# 03_ICs.net
KiCad netlist of a schematic drawn in Altium Designer
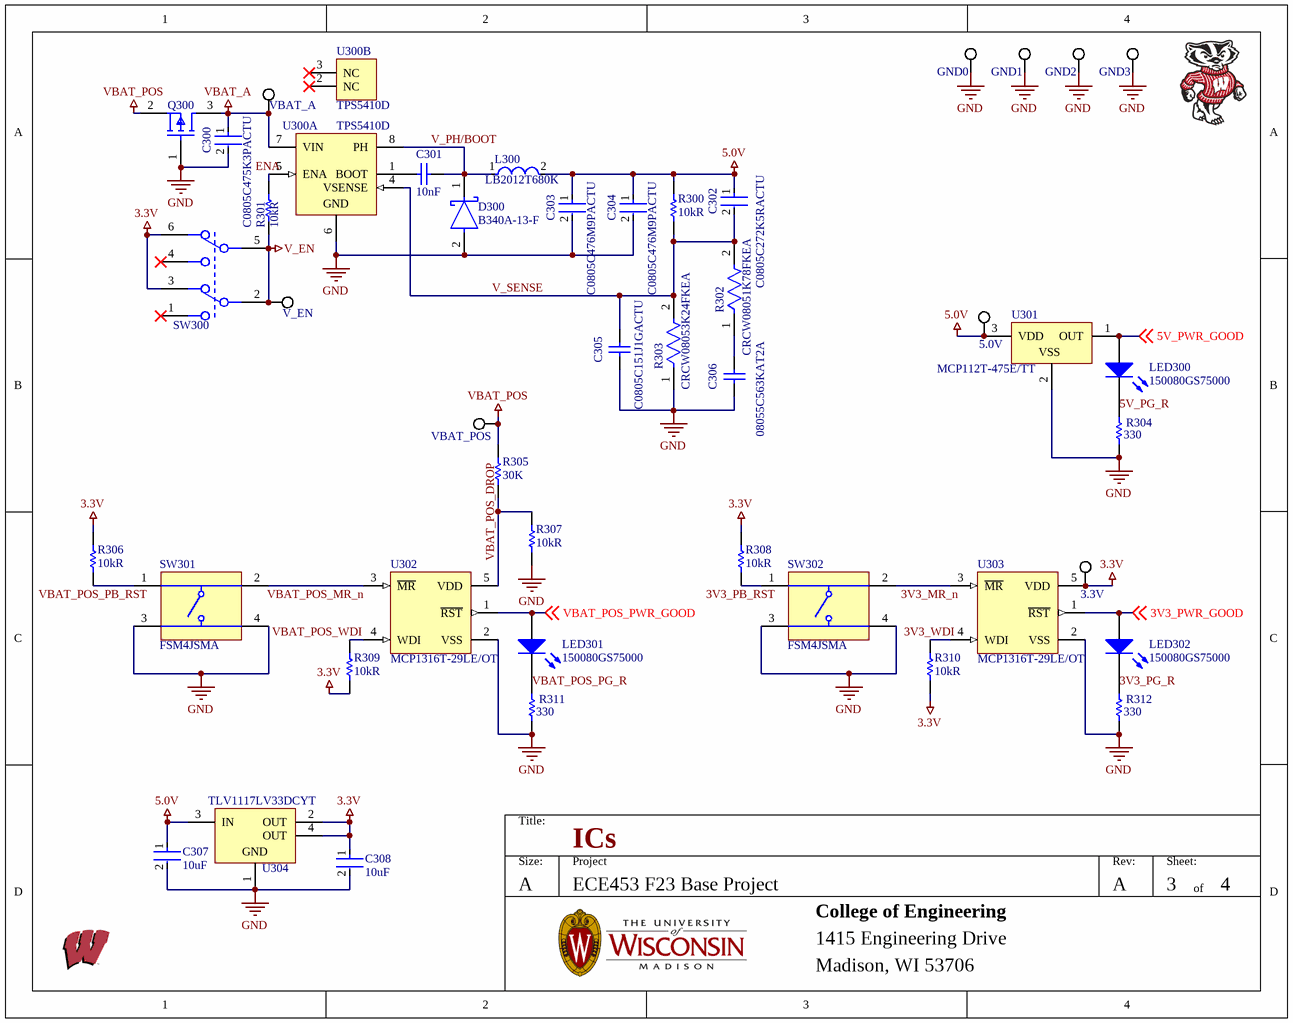
[diagram p0: 03_ICs.SchDoc]

(export (version "E")
  (design (tool "Eeschema 10.0.6"))
  (components
    (comp (ref "3.3V")
      (value "5019")
      (footprint "KSTN-5019_V")
      (description "Test Point, 1 Position SMD, RoHS, Tape and Reel")
      (fields (field (name "MANUFACTURER") "Keystone Electronics"))
      (libsource (lib "ECE453") (part "CMP-1672-00008-1"))
    )
    (comp (ref "5.0V")
      (value "5019")
      (footprint "KSTN-5019_V")
      (description "Test Point, 1 Position SMD, RoHS, Tape and Reel")
      (fields (field (name "MANUFACTURER") "Keystone Electronics"))
      (libsource (lib "ECE453") (part "CMP-1672-00008-1"))
    )
    (comp (ref "C300")
      (value "C0805C475K3PACTU")
      (footprint "FP-C0805C475K3PACTU-MFG")
      (description "CAP CER 4.7UF 25V X5R 0805")
      (fields (field (name "TOLERANCE") "10%") (field (name "VOLTAGE") "25V"))
      (libsource (lib "Altium Content Vault") (part "02cd4be3c70576c341d710602a673aa"))
    )
    (comp (ref "C301")
      (value "10nF")
      (footprint "CAP_0805")
      (description "Cap Ceramic 0.01uF 100V X7R 10% SMD 0805 125°C Plastic T/R")
      (fields
        (field (name "MANUFACTURER") "KEMET")
        (field (name "MANUFACTURER PART NUMBER") "C0805C103K1RAC7210")
      )
      (libsource (lib "ECE453") (part "Cap_4"))
    )
    (comp (ref "C302")
      (value "C0805C272K5RACTU")
      (footprint "FP-C0805C-DN-MFG")
      (description "0805 C 2.7nF Ceramic Multilayer Capacitor; 50 VDC; +125degC; X7R Dielec; +/-10%")
      (fields
        (field (name "TOLERANCE") "0.1")
        (field (name "OCTOPART") "https://octopart.com/c0805c272k5ractu-kemet-135930")
      )
      (libsource (lib "Altium Content Vault") (part "b4654b650e69147ec39a6b967a45e02"))
    )
    (comp (ref "C303")
      (value "C0805C476M9PACTU")
      (footprint "FP-C0805C476M9PACTU-MFG")
      (description "CAP CER 47UF 6.3V X5R 0805")
      (fields (field (name "VOLTAGE") "6.3V") (field (name "TOLERANCE") "20%"))
      (libsource (lib "Altium Content Vault") (part "11868f565c42a9108669ba33697ecf6"))
    )
    (comp (ref "C304")
      (value "C0805C476M9PACTU")
      (footprint "FP-C0805C476M9PACTU-MFG")
      (description "CAP CER 47UF 6.3V X5R 0805")
      (fields (field (name "VOLTAGE") "6.3V") (field (name "TOLERANCE") "20%"))
      (libsource (lib "Altium Content Vault") (part "11868f565c42a9108669ba33697ecf6"))
    )
    (comp (ref "C305")
      (value "C0805C151J1GACTU")
      (footprint "CAPC2013X88X50NL20T25")
      (fields (field (name "MANUFACTURER") "Kemet"))
      (libsource (lib "Altium Content Vault") (part "CAP"))
    )
    (comp (ref "C306")
      (value "08055C563KAT2A")
      (footprint "CAPC2013X94X50NL20T25")
      (fields (field (name "MANUFACTURER") "AVX Interconnect / Elco"))
      (libsource (lib "Altium Content Vault") (part "CAP"))
    )
    (comp (ref "C307")
      (value "10uF")
      (footprint "FP-C0805C-DG-MFG")
      (description "CAP CER 10UF 10V X5R 0805")
      (fields
        (field (name "MANUFACTURER") "KEMET")
        (field (name "MANUFACTURER PART NUMBER") "C0805C106K8PACTU")
      )
      (libsource (lib "ECE453") (part "CMP-2007-03243-2"))
    )
    (comp (ref "C308")
      (value "10uF")
      (footprint "FP-C0805C-DG-MFG")
      (description "CAP CER 10UF 10V X5R 0805")
      (fields
        (field (name "MANUFACTURER") "KEMET")
        (field (name "MANUFACTURER PART NUMBER") "C0805C106K8PACTU")
      )
      (libsource (lib "ECE453") (part "CMP-2007-03243-2"))
    )
    (comp (ref "D300")
      (value "B340A-13-F")
      (footprint "FP-SMA-MFG")
      (description "DIODE SCHOTTKY 40V 3A SMA")
      (fields (field (name "VOLTAGE") "40V") (field (name "MANUFACTURER") "Diodes"))
      (libsource (lib "Altium Content Vault") (part "1d6ec82d83fb6aee721767c19dac4b9"))
    )
    (comp (ref "GND0")
      (value "5019")
      (footprint "KSTN-5019_V")
      (description "Test Point, 1 Position SMD, RoHS, Tape and Reel")
      (fields (field (name "MANUFACTURER") "Keystone Electronics"))
      (libsource (lib "ECE453") (part "CMP-1672-00008-1"))
    )
    (comp (ref "GND1")
      (value "5019")
      (footprint "KSTN-5019_V")
      (description "Test Point, 1 Position SMD, RoHS, Tape and Reel")
      (fields (field (name "MANUFACTURER") "Keystone Electronics"))
      (libsource (lib "ECE453") (part "CMP-1672-00008-1"))
    )
    (comp (ref "GND2")
      (value "5019")
      (footprint "KSTN-5019_V")
      (description "Test Point, 1 Position SMD, RoHS, Tape and Reel")
      (fields (field (name "MANUFACTURER") "Keystone Electronics"))
      (libsource (lib "ECE453") (part "CMP-1672-00008-1"))
    )
    (comp (ref "GND3")
      (value "5019")
      (footprint "KSTN-5019_V")
      (description "Test Point, 1 Position SMD, RoHS, Tape and Reel")
      (fields (field (name "MANUFACTURER") "Keystone Electronics"))
      (libsource (lib "ECE453") (part "CMP-1672-00008-1"))
    )
    (comp (ref "L300")
      (value "LB2012T680K")
      (footprint "FP-LB2012-1_25-0_2-IPC_A")
      (description "SMD Inductors 68uH ±10% 0.05A 7.8Ω 0805")
      (fields (field (name "TOLERANCE") "10%") (field (name "MANUFACTURER") "Taiyo Yuden"))
      (libsource (lib "Altium Content Vault") (part "725321dda6339637d4d059423bc1c3c"))
    )
    (comp (ref "LED300")
      (value "150080GS75000")
      (footprint "0805_A")
      (description "SMD mono-color Chip LED, WL-SMCW, Green")
      (fields (field (name "MANUFACTURER") "Wuerth Elektronik"))
      (libsource (lib "ECE453") (part "CMP-1426-00007-1"))
    )
    (comp (ref "LED301")
      (value "150080GS75000")
      (footprint "0805_A")
      (description "SMD mono-color Chip LED, WL-SMCW, Green")
      (fields (field (name "MANUFACTURER") "Wuerth Elektronik"))
      (libsource (lib "ECE453") (part "CMP-1426-00007-1"))
    )
    (comp (ref "LED302")
      (value "150080GS75000")
      (footprint "0805_A")
      (description "SMD mono-color Chip LED, WL-SMCW, Green")
      (fields (field (name "MANUFACTURER") "Wuerth Elektronik"))
      (libsource (lib "ECE453") (part "CMP-1426-00007-1"))
    )
    (comp (ref "Q300")
      (value "SSM3J328R,LF")
      (footprint "SOT-23_M")
      (description "MOSFET P-CH 20V 6A SOT23F")
      (libsource (lib "ECE453") (part "SSM3J328R,LF"))
    )
    (comp (ref "R300")
      (value "RC0805FR-0710KL")
      (footprint "RESC2013X60X35NL10T20")
      (description "Chip Resistor, 10 KOhm, +/- 1%, 0.125 W, -55 to 155 degC, 0805 (2012 Metric), RoHS, Tape and Reel")
      (fields
        (field (name "MANUFACTURER") "Yageo")
        (field (name "TOLERANCE") "1%")
        (field (name "RESISTANCE") "10kR")
      )
      (libsource (lib "ECE453") (part "CMP-1659-00013-4"))
    )
    (comp (ref "R301")
      (value "RC0805FR-0710KL")
      (footprint "RESC2013X60X35NL10T20")
      (description "Chip Resistor, 10 KOhm, +/- 1%, 0.125 W, -55 to 155 degC, 0805 (2012 Metric), RoHS, Tape and Reel")
      (fields
        (field (name "MANUFACTURER") "Yageo")
        (field (name "TOLERANCE") "1%")
        (field (name "RESISTANCE") "10kR")
      )
      (libsource (lib "ECE453") (part "CMP-1659-00013-4"))
    )
    (comp (ref "R302")
      (value "CRCW08051K78FKEA")
      (footprint "FP-CRCW0805-e3-IPC_C")
      (description "RES Thick Film, 1.78kΩ, 1%, 0.125W, 100ppm/°C, 0805")
      (fields (field (name "TOLERANCE") "1%") (field (name "MANUFACTURER") "Vishay"))
      (libsource (lib "Altium Content Vault") (part "1029c3af85768c4190bb7ad29bc67b5"))
    )
    (comp (ref "R303")
      (value "CRCW08053K24FKEA")
      (footprint "FP-CRCW0805-e3-IPC_C")
      (description "RES Thick Film, 3.24kΩ, 1%, 0.125W, 100ppm/°C, 0805")
      (fields (field (name "TOLERANCE") "1%") (field (name "MANUFACTURER") "Vishay"))
      (libsource (lib "Altium Content Vault") (part "1029c3af85768c4190bb7ad29bc67b5"))
    )
    (comp (ref "R304")
      (value "RC0805FR-07330RL")
      (footprint "RESC2013X60X35LL10T20")
      (description "Chip Resistor, 330 Ohm, +/- 1%, 125 mW, -55 to 155 degC, 0805 (2012 Metric), RoHS, Tape and Reel")
      (fields
        (field (name "MANUFACTURER") "Yageo")
        (field (name "TOLERANCE") "1%")
        (field (name "RESISTANCE") "330")
      )
      (libsource (lib "ECE453") (part "CMP-2000-06960-1"))
    )
    (comp (ref "R305")
      (value "30K")
      (footprint "RES_0805")
      (description "Res Thick Film 0805 30K Ohm 1% 0.125W(1/8W) ±100ppm/°C Pad SMD Automotive T/R")
      (fields (field (name "TOLERANCE") "1%") (field (name "RESISTANCE") "30K"))
      (libsource (lib "ECE453") (part "RES_0805_K_030.00"))
    )
    (comp (ref "R306")
      (value "RC0805FR-0710KL")
      (footprint "RESC2013X60X35NL10T20")
      (description "Chip Resistor, 10 KOhm, +/- 1%, 0.125 W, -55 to 155 degC, 0805 (2012 Metric), RoHS, Tape and Reel")
      (fields
        (field (name "MANUFACTURER") "Yageo")
        (field (name "TOLERANCE") "1%")
        (field (name "RESISTANCE") "10kR")
      )
      (libsource (lib "ECE453") (part "CMP-1659-00013-4"))
    )
    (comp (ref "R307")
      (value "RC0805FR-0710KL")
      (footprint "RESC2013X60X35NL10T20")
      (description "Chip Resistor, 10 KOhm, +/- 1%, 0.125 W, -55 to 155 degC, 0805 (2012 Metric), RoHS, Tape and Reel")
      (fields
        (field (name "MANUFACTURER") "Yageo")
        (field (name "TOLERANCE") "1%")
        (field (name "RESISTANCE") "10kR")
      )
      (libsource (lib "ECE453") (part "CMP-1659-00013-4"))
    )
    (comp (ref "R308")
      (value "RC0805FR-0710KL")
      (footprint "RESC2013X60X35NL10T20")
      (description "Chip Resistor, 10 KOhm, +/- 1%, 0.125 W, -55 to 155 degC, 0805 (2012 Metric), RoHS, Tape and Reel")
      (fields
        (field (name "MANUFACTURER") "Yageo")
        (field (name "TOLERANCE") "1%")
        (field (name "RESISTANCE") "10kR")
      )
      (libsource (lib "ECE453") (part "CMP-1659-00013-4"))
    )
    (comp (ref "R309")
      (value "RC0805FR-0710KL")
      (footprint "RESC2013X60X35NL10T20")
      (description "Chip Resistor, 10 KOhm, +/- 1%, 0.125 W, -55 to 155 degC, 0805 (2012 Metric), RoHS, Tape and Reel")
      (fields
        (field (name "MANUFACTURER") "Yageo")
        (field (name "TOLERANCE") "1%")
        (field (name "RESISTANCE") "10kR")
      )
      (libsource (lib "ECE453") (part "CMP-1659-00013-4"))
    )
    (comp (ref "R310")
      (value "RC0805FR-0710KL")
      (footprint "RESC2013X60X35NL10T20")
      (description "Chip Resistor, 10 KOhm, +/- 1%, 0.125 W, -55 to 155 degC, 0805 (2012 Metric), RoHS, Tape and Reel")
      (fields
        (field (name "MANUFACTURER") "Yageo")
        (field (name "TOLERANCE") "1%")
        (field (name "RESISTANCE") "10kR")
      )
      (libsource (lib "ECE453") (part "CMP-1659-00013-4"))
    )
    (comp (ref "R311")
      (value "RC0805FR-07330RL")
      (footprint "RESC2013X60X35LL10T20")
      (description "Chip Resistor, 330 Ohm, +/- 1%, 125 mW, -55 to 155 degC, 0805 (2012 Metric), RoHS, Tape and Reel")
      (fields
        (field (name "MANUFACTURER") "Yageo")
        (field (name "TOLERANCE") "1%")
        (field (name "RESISTANCE") "330")
      )
      (libsource (lib "ECE453") (part "CMP-2000-06960-1"))
    )
    (comp (ref "R312")
      (value "RC0805FR-07330RL")
      (footprint "RESC2013X60X35LL10T20")
      (description "Chip Resistor, 330 Ohm, +/- 1%, 125 mW, -55 to 155 degC, 0805 (2012 Metric), RoHS, Tape and Reel")
      (fields
        (field (name "MANUFACTURER") "Yageo")
        (field (name "TOLERANCE") "1%")
        (field (name "RESISTANCE") "330")
      )
      (libsource (lib "ECE453") (part "CMP-2000-06960-1"))
    )
    (comp (ref "SW300")
      (value "JS202011SCQN")
      (footprint "C&K_Components_0_MFG")
      (description "C & K COMPONENTS - JS202011SCQN - SWITCH, DPDT, 0.6A, 6VDC, SMD")
      (libsource (lib "ECE453") (part "JS202011SCQN"))
    )
    (comp (ref "SW301")
      (value "FSM4JSMA")
      (footprint "TECO-FSM4JSMA_V")
      (description "Swicth, SPST, 24 V, -35 to 85 degC, 4-Pin SMD, RoHS, Tape and Reel")
      (fields (field (name "MANUFACTURER") "TE Connectivity"))
      (libsource (lib "ECE453") (part "CMP-2000-05602-2"))
    )
    (comp (ref "SW302")
      (value "FSM4JSMA")
      (footprint "TECO-FSM4JSMA_V")
      (description "Swicth, SPST, 24 V, -35 to 85 degC, 4-Pin SMD, RoHS, Tape and Reel")
      (fields (field (name "MANUFACTURER") "TE Connectivity"))
      (libsource (lib "ECE453") (part "CMP-2000-05602-2"))
    )
    (comp (ref "U300")
      (value "TPS5410D")
      (footprint "D0008A_N")
      (fields (field (name "MANUFACTURER") "Texas Instruments"))
      (libsource (lib "Altium Content Vault") (part "TI-TPS5410D8"))
    )
    (comp (ref "U301")
      (value "MCP112T-475E/TT")
      (footprint "SOT-23-TT3_L")
      (fields (field (name "MANUFACTURER") "Microchip"))
      (libsource (lib "Altium Content Vault") (part "PM-VLTD-MCP11X-SOT3"))
    )
    (comp (ref "U302")
      (value "MCP1316T-29LE/OT")
      (footprint "SOT-23-OT5_M")
      (description "Voltage Supervisor, 5-Pin SOT-23, Extended Temperature, Tape and Reel")
      (fields (field (name "MANUFACTURER") "Microchip"))
      (libsource (lib "ECE453") (part "CMP-0138-00207-1"))
    )
    (comp (ref "U303")
      (value "MCP1316T-29LE/OT")
      (footprint "SOT-23-OT5_M")
      (description "Voltage Supervisor, 5-Pin SOT-23, Extended Temperature, Tape and Reel")
      (fields (field (name "MANUFACTURER") "Microchip"))
      (libsource (lib "ECE453") (part "CMP-0138-00207-1"))
    )
    (comp (ref "U304")
      (value "TLV1117LV33DCYT")
      (footprint "DCY0004A_M")
      (fields
        (field (name "MANUFACTURER") "Texas Instruments")
        (field (name "MANUFACTURER PART NUMBER") "TLV1117-33CDCYR")
      )
      (libsource (lib "ECE453") (part "CMP-0395-00499-2"))
    )
    (comp (ref "VBAT_A")
      (value "5019")
      (footprint "KSTN-5019_V")
      (description "Test Point, 1 Position SMD, RoHS, Tape and Reel")
      (fields (field (name "MANUFACTURER") "Keystone Electronics"))
      (libsource (lib "ECE453") (part "CMP-1672-00008-1"))
    )
    (comp (ref "VBAT_POS")
      (value "5019")
      (footprint "KSTN-5019_V")
      (description "Test Point, 1 Position SMD, RoHS, Tape and Reel")
      (fields (field (name "MANUFACTURER") "Keystone Electronics"))
      (libsource (lib "ECE453") (part "CMP-1672-00008-1"))
    )
    (comp (ref "V_EN")
      (value "5019")
      (footprint "KSTN-5019_V")
      (description "Test Point, 1 Position SMD, RoHS, Tape and Reel")
      (fields (field (name "MANUFACTURER") "Keystone Electronics"))
      (libsource (lib "ECE453") (part "CMP-1672-00008-1"))
    )
  )
  (nets
    (net (code "1") (name "/3V3_MR_n") (class "Default")
      (node (ref "SW302") (pin "2") (pinfunction "2_2") (pintype "passive"))
      (node (ref "U303") (pin "3") (pinfunction "~{MR}_3") (pintype "input"))
    )
    (net (code "2") (name "/3V3_PB_RST") (class "Default")
      (node (ref "R308") (pin "1") (pinfunction "1_1") (pintype "passive"))
      (node (ref "SW302") (pin "1") (pinfunction "1_1") (pintype "passive"))
    )
    (net (code "3") (name "/3V3_PG_R") (class "Default")
      (node (ref "LED302") (pin "1") (pinfunction "K_1") (pintype "passive"))
      (node (ref "R312") (pin "2") (pinfunction "2_2") (pintype "passive"))
    )
    (net (code "4") (name "/3V3_WDI") (class "Default")
      (node (ref "R310") (pin "2") (pinfunction "2_2") (pintype "passive"))
      (node (ref "U303") (pin "4") (pinfunction "WDI_4") (pintype "input"))
    )
    (net (code "5") (name "/5V_PG_R") (class "Default")
      (node (ref "LED300") (pin "1") (pinfunction "K_1") (pintype "passive"))
      (node (ref "R304") (pin "2") (pinfunction "2_2") (pintype "passive"))
    )
    (net (code "6") (name "/ENA") (class "Default")
      (node (ref "R301") (pin "2") (pinfunction "2_2") (pintype "passive"))
      (node (ref "U300") (pin "5") (pinfunction "ENA_5") (pintype "input"))
    )
    (net (code "7") (name "/VBAT_POS_DROP") (class "Default")
      (node (ref "R305") (pin "1") (pinfunction "1_1") (pintype "passive"))
      (node (ref "R307") (pin "2") (pinfunction "2_2") (pintype "passive"))
      (node (ref "U302") (pin "5") (pinfunction "VDD_5") (pintype "power_in"))
    )
    (net (code "8") (name "/VBAT_POS_MR_n") (class "Default")
      (node (ref "SW301") (pin "2") (pinfunction "2_2") (pintype "passive"))
      (node (ref "U302") (pin "3") (pinfunction "~{MR}_3") (pintype "input"))
    )
    (net (code "9") (name "/VBAT_POS_PB_RST") (class "Default")
      (node (ref "R306") (pin "1") (pinfunction "1_1") (pintype "passive"))
      (node (ref "SW301") (pin "1") (pinfunction "1_1") (pintype "passive"))
    )
    (net (code "10") (name "/VBAT_POS_PG_R") (class "Default")
      (node (ref "LED301") (pin "1") (pinfunction "K_1") (pintype "passive"))
      (node (ref "R311") (pin "2") (pinfunction "2_2") (pintype "passive"))
    )
    (net (code "11") (name "/VBAT_POS_WDI") (class "Default")
      (node (ref "R309") (pin "2") (pinfunction "2_2") (pintype "passive"))
      (node (ref "U302") (pin "4") (pinfunction "WDI_4") (pintype "input"))
    )
    (net (code "12") (name "/V_PH{slash}BOOT") (class "Default")
      (node (ref "C301") (pin "2") (pinfunction "2_2") (pintype "passive"))
      (node (ref "D300") (pin "1") (pinfunction "C_1") (pintype "passive"))
      (node (ref "L300") (pin "1") (pinfunction "1_1") (pintype "passive"))
      (node (ref "U300") (pin "8") (pinfunction "PH_8") (pintype "power_in"))
    )
    (net (code "13") (name "/V_SENSE") (class "Default")
      (node (ref "C302") (pin "2") (pinfunction "2_2") (pintype "passive"))
      (node (ref "C305") (pin "2") (pinfunction "2_2") (pintype "passive"))
      (node (ref "R300") (pin "2") (pinfunction "2_2") (pintype "passive"))
      (node (ref "R302") (pin "2") (pinfunction "2_2") (pintype "passive"))
      (node (ref "R303") (pin "2") (pinfunction "2_2") (pintype "passive"))
      (node (ref "U300") (pin "4") (pinfunction "VSENSE_4") (pintype "input"))
    )
    (net (code "14") (name "3.3V") (class "Default")
      (node (ref "3.3V") (pin "1") (pinfunction "1_1") (pintype "passive"))
      (node (ref "C308") (pin "1") (pinfunction "1_1") (pintype "passive"))
      (node (ref "R306") (pin "2") (pinfunction "2_2") (pintype "passive"))
      (node (ref "R308") (pin "2") (pinfunction "2_2") (pintype "passive"))
      (node (ref "R309") (pin "1") (pinfunction "1_1") (pintype "passive"))
      (node (ref "R310") (pin "1") (pinfunction "1_1") (pintype "passive"))
      (node (ref "SW300") (pin "3") (pinfunction "3_3") (pintype "passive"))
      (node (ref "SW300") (pin "6") (pinfunction "6_6") (pintype "passive"))
      (node (ref "U303") (pin "5") (pinfunction "VDD_5") (pintype "power_in"))
      (node (ref "U304") (pin "2") (pinfunction "OUT_2") (pintype "power_in"))
      (node (ref "U304") (pin "4") (pinfunction "OUT_4") (pintype "power_in"))
    )
    (net (code "15") (name "3V3_PWR_GOOD") (class "Default")
      (node (ref "LED302") (pin "2") (pinfunction "A_2") (pintype "passive"))
      (node (ref "U303") (pin "1") (pinfunction "~{RST}_1") (pintype "output"))
    )
    (net (code "16") (name "5.0V") (class "Default")
      (node (ref "5.0V") (pin "1") (pinfunction "1_1") (pintype "passive"))
      (node (ref "C302") (pin "1") (pinfunction "1_1") (pintype "passive"))
      (node (ref "C303") (pin "1") (pinfunction "1_1") (pintype "passive"))
      (node (ref "C304") (pin "1") (pinfunction "1_1") (pintype "passive"))
      (node (ref "C307") (pin "1") (pinfunction "1_1") (pintype "passive"))
      (node (ref "L300") (pin "2") (pinfunction "2_2") (pintype "passive"))
      (node (ref "R300") (pin "1") (pinfunction "1_1") (pintype "passive"))
      (node (ref "U301") (pin "3") (pinfunction "VDD_3") (pintype "power_in"))
      (node (ref "U304") (pin "3") (pinfunction "IN_3") (pintype "power_in"))
    )
    (net (code "17") (name "5V_PWR_GOOD") (class "Default")
      (node (ref "LED300") (pin "2") (pinfunction "A_2") (pintype "passive"))
      (node (ref "U301") (pin "1") (pinfunction "OUT_1") (pintype "power_in"))
    )
    (net (code "18") (name "GND") (class "Default")
      (node (ref "C300") (pin "2") (pinfunction "2_2") (pintype "passive"))
      (node (ref "C303") (pin "2") (pinfunction "2_2") (pintype "passive"))
      (node (ref "C304") (pin "2") (pinfunction "2_2") (pintype "passive"))
      (node (ref "C305") (pin "1") (pinfunction "1_1") (pintype "passive"))
      (node (ref "C306") (pin "1") (pinfunction "1_1") (pintype "passive"))
      (node (ref "C307") (pin "2") (pinfunction "2_2") (pintype "passive"))
      (node (ref "C308") (pin "2") (pinfunction "2_2") (pintype "passive"))
      (node (ref "D300") (pin "2") (pinfunction "A_2") (pintype "passive"))
      (node (ref "GND0") (pin "1") (pinfunction "1_1") (pintype "passive"))
      (node (ref "GND1") (pin "1") (pinfunction "1_1") (pintype "passive"))
      (node (ref "GND2") (pin "1") (pinfunction "1_1") (pintype "passive"))
      (node (ref "GND3") (pin "1") (pinfunction "1_1") (pintype "passive"))
      (node (ref "Q300") (pin "1") (pinfunction "Gate_1") (pintype "passive"))
      (node (ref "R303") (pin "1") (pinfunction "1_1") (pintype "passive"))
      (node (ref "R304") (pin "1") (pinfunction "1_1") (pintype "passive"))
      (node (ref "R307") (pin "1") (pinfunction "1_1") (pintype "passive"))
      (node (ref "R311") (pin "1") (pinfunction "1_1") (pintype "passive"))
      (node (ref "R312") (pin "1") (pinfunction "1_1") (pintype "passive"))
      (node (ref "SW301") (pin "3") (pinfunction "3_3") (pintype "passive"))
      (node (ref "SW301") (pin "4") (pinfunction "4_4") (pintype "passive"))
      (node (ref "SW302") (pin "3") (pinfunction "3_3") (pintype "passive"))
      (node (ref "SW302") (pin "4") (pinfunction "4_4") (pintype "passive"))
      (node (ref "U300") (pin "6") (pinfunction "GND_6") (pintype "power_in"))
      (node (ref "U301") (pin "2") (pinfunction "VSS_2") (pintype "power_in"))
      (node (ref "U302") (pin "2") (pinfunction "VSS_2") (pintype "power_in"))
      (node (ref "U303") (pin "2") (pinfunction "VSS_2") (pintype "power_in"))
      (node (ref "U304") (pin "1") (pinfunction "GND_1") (pintype "power_in"))
    )
    (net (code "19") (name "Net-(C306-Pad2)") (class "Default")
      (node (ref "C306") (pin "2") (pinfunction "2_2") (pintype "passive"))
      (node (ref "R302") (pin "1") (pinfunction "1_1") (pintype "passive"))
    )
    (net (code "20") (name "Net-(U300A-BOOT)") (class "Default")
      (node (ref "C301") (pin "1") (pinfunction "1_1") (pintype "passive"))
      (node (ref "U300") (pin "1") (pinfunction "BOOT_1") (pintype "passive"))
    )
    (net (code "21") (name "VBAT_A") (class "Default")
      (node (ref "C300") (pin "1") (pinfunction "1_1") (pintype "passive"))
      (node (ref "Q300") (pin "3") (pinfunction "Drain_3") (pintype "passive"))
      (node (ref "U300") (pin "7") (pinfunction "VIN_7") (pintype "power_in"))
      (node (ref "VBAT_A") (pin "1") (pinfunction "1_1") (pintype "passive"))
    )
    (net (code "22") (name "VBAT_POS") (class "Default")
      (node (ref "Q300") (pin "2") (pinfunction "Source_2") (pintype "passive"))
      (node (ref "R305") (pin "2") (pinfunction "2_2") (pintype "passive"))
      (node (ref "VBAT_POS") (pin "1") (pinfunction "1_1") (pintype "passive"))
    )
    (net (code "23") (name "VBAT_POS_PWR_GOOD") (class "Default")
      (node (ref "LED301") (pin "2") (pinfunction "A_2") (pintype "passive"))
      (node (ref "U302") (pin "1") (pinfunction "~{RST}_1") (pintype "output"))
    )
    (net (code "24") (name "V_EN") (class "Default")
      (node (ref "R301") (pin "1") (pinfunction "1_1") (pintype "passive"))
      (node (ref "SW300") (pin "2") (pinfunction "2_2") (pintype "passive"))
      (node (ref "SW300") (pin "5") (pinfunction "5_5") (pintype "passive"))
      (node (ref "V_EN") (pin "1") (pinfunction "1_1") (pintype "passive"))
    )
    (net (code "25") (name "unconnected-(SW300-Pad1)") (class "Default")
      (node (ref "SW300") (pin "1") (pinfunction "1_1") (pintype "passive+no_connect"))
    )
    (net (code "26") (name "unconnected-(SW300-Pad4)") (class "Default")
      (node (ref "SW300") (pin "4") (pinfunction "4_4") (pintype "passive+no_connect"))
    )
    (net (code "27") (name "unconnected-(U300B-NC-Pad2)") (class "Default")
      (node (ref "U300") (pin "2") (pinfunction "NC_2") (pintype "passive+no_connect"))
    )
    (net (code "28") (name "unconnected-(U300B-NC-Pad3)") (class "Default")
      (node (ref "U300") (pin "3") (pinfunction "NC_3") (pintype "passive+no_connect"))
    )
  )
)
